# MOTOR_DRIVERS.net
KiCad netlist of a schematic drawn in Altium Designer
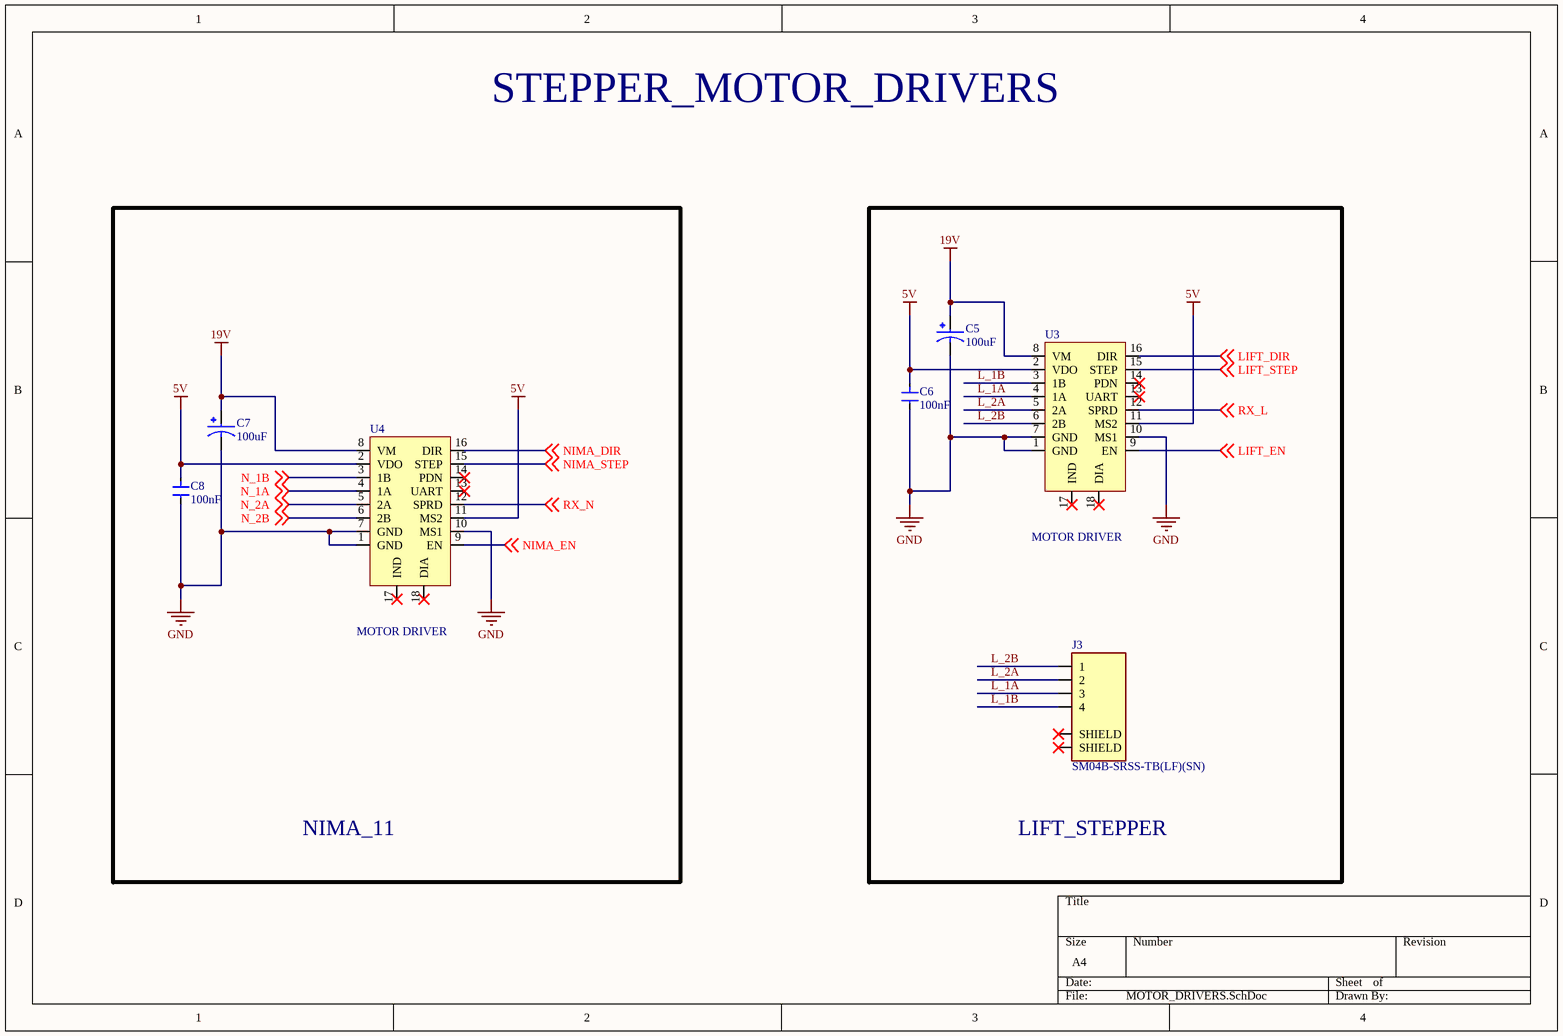
[diagram p0: MOTOR_DRIVERS.SchDoc]

(export (version "E")
  (design (tool "Eeschema 10.0.6"))
  (components
    (comp (ref "C5")
      (value "100uF")
      (footprint "CAP_EEEFTH101XAP")
      (description "100ÂµF 50V Aluminum Electrolytic Capacitors Radial, Can - SMD 340mOhm @ 100kHz 2000 Hrs @ 105Â°C")
      (fields (field (name "PART NUMBER") "EEEFTH101XAP"))
      (libsource (lib "Schlib2") (part "EEEFTH101XAP"))
    )
    (comp (ref "C6")
      (value "100nF")
      (footprint "CAP 0603")
      (fields (field (name "PART NUMBER") "CC0603JRX7R9BB104"))
      (libsource (lib "Schlib2") (part "Capasitor"))
    )
    (comp (ref "C7")
      (value "100uF")
      (footprint "CAP_EEEFTH101XAP")
      (description "100ÂµF 50V Aluminum Electrolytic Capacitors Radial, Can - SMD 340mOhm @ 100kHz 2000 Hrs @ 105Â°C")
      (fields (field (name "PART NUMBER") "EEEFTH101XAP"))
      (libsource (lib "Schlib2") (part "EEEFTH101XAP"))
    )
    (comp (ref "C8")
      (value "100nF")
      (footprint "CAP 0603")
      (fields (field (name "PART NUMBER") "CC0603JRX7R9BB104"))
      (libsource (lib "Schlib2") (part "Capasitor"))
    )
    (comp (ref "J3")
      (value "SM04B-SRSS-TB(LF)(SN)")
      (footprint "CONN-TH_B4B-PH-K-S")
      (description "Connector Header Surface Mount, Right Angle 4 position 0.039 (1.00mm)")
      (fields (field (name "PART NUMBER") "B4B-PH-K-S(LF)(SN)"))
      (libsource (lib "Schlib2") (part "SM04B-SRSS-TB(LF)(SN)"))
    )
    (comp (ref "U3")
      (value "MOTOR DRIVER")
      (footprint "MOTOR DRIVER")
      (libsource (lib "Schlib2") (part "MOTOR DRIVER"))
    )
    (comp (ref "U4")
      (value "MOTOR DRIVER")
      (footprint "MOTOR DRIVER")
      (libsource (lib "Schlib2") (part "MOTOR DRIVER"))
    )
  )
  (nets
    (net (code "1") (name "/L_1A") (class "Default")
      (node (ref "J3") (pin "3") (pinfunction "3_3") (pintype "passive"))
      (node (ref "U3") (pin "4") (pinfunction "1A_4") (pintype "passive"))
    )
    (net (code "2") (name "/L_1B") (class "Default")
      (node (ref "J3") (pin "4") (pinfunction "4_4") (pintype "passive"))
      (node (ref "U3") (pin "3") (pinfunction "1B_3") (pintype "passive"))
    )
    (net (code "3") (name "/L_2A") (class "Default")
      (node (ref "J3") (pin "2") (pinfunction "2_2") (pintype "passive"))
      (node (ref "U3") (pin "5") (pinfunction "2A_5") (pintype "passive"))
    )
    (net (code "4") (name "/L_2B") (class "Default")
      (node (ref "J3") (pin "1") (pinfunction "1_1") (pintype "passive"))
      (node (ref "U3") (pin "6") (pinfunction "2B_6") (pintype "passive"))
    )
    (net (code "5") (name "5V") (class "Default")
      (node (ref "C6") (pin "1") (pinfunction "1_1") (pintype "passive"))
      (node (ref "C8") (pin "1") (pinfunction "1_1") (pintype "passive"))
      (node (ref "U3") (pin "11") (pinfunction "MS2_11") (pintype "passive"))
      (node (ref "U3") (pin "2") (pinfunction "VDO_2") (pintype "passive"))
      (node (ref "U4") (pin "11") (pinfunction "MS2_11") (pintype "passive"))
      (node (ref "U4") (pin "2") (pinfunction "VDO_2") (pintype "passive"))
    )
    (net (code "6") (name "19V") (class "Default")
      (node (ref "C5") (pin "1") (pinfunction "1_1") (pintype "passive"))
      (node (ref "C7") (pin "1") (pinfunction "1_1") (pintype "passive"))
      (node (ref "U3") (pin "8") (pinfunction "VM_8") (pintype "passive"))
      (node (ref "U4") (pin "8") (pinfunction "VM_8") (pintype "passive"))
    )
    (net (code "7") (name "GND") (class "Default")
      (node (ref "C5") (pin "2") (pinfunction "2_2") (pintype "passive"))
      (node (ref "C6") (pin "2") (pinfunction "2_2") (pintype "passive"))
      (node (ref "C7") (pin "2") (pinfunction "2_2") (pintype "passive"))
      (node (ref "C8") (pin "2") (pinfunction "2_2") (pintype "passive"))
      (node (ref "U3") (pin "1") (pinfunction "GND_1") (pintype "passive"))
      (node (ref "U3") (pin "10") (pinfunction "MS1_10") (pintype "passive"))
      (node (ref "U3") (pin "7") (pinfunction "GND_7") (pintype "passive"))
      (node (ref "U4") (pin "1") (pinfunction "GND_1") (pintype "passive"))
      (node (ref "U4") (pin "10") (pinfunction "MS1_10") (pintype "passive"))
      (node (ref "U4") (pin "7") (pinfunction "GND_7") (pintype "passive"))
    )
    (net (code "8") (name "LIFT_DIR") (class "Default")
      (node (ref "U3") (pin "16") (pinfunction "DIR_16") (pintype "passive"))
    )
    (net (code "9") (name "LIFT_EN") (class "Default")
      (node (ref "U3") (pin "9") (pinfunction "EN_9") (pintype "passive"))
    )
    (net (code "10") (name "LIFT_STEP") (class "Default")
      (node (ref "U3") (pin "15") (pinfunction "STEP_15") (pintype "passive"))
    )
    (net (code "11") (name "NIMA_DIR") (class "Default")
      (node (ref "U4") (pin "16") (pinfunction "DIR_16") (pintype "passive"))
    )
    (net (code "12") (name "NIMA_EN") (class "Default")
      (node (ref "U4") (pin "9") (pinfunction "EN_9") (pintype "passive"))
    )
    (net (code "13") (name "NIMA_STEP") (class "Default")
      (node (ref "U4") (pin "15") (pinfunction "STEP_15") (pintype "passive"))
    )
    (net (code "14") (name "N_1A") (class "Default")
      (node (ref "U4") (pin "4") (pinfunction "1A_4") (pintype "passive"))
    )
    (net (code "15") (name "N_1B") (class "Default")
      (node (ref "U4") (pin "3") (pinfunction "1B_3") (pintype "passive"))
    )
    (net (code "16") (name "N_2A") (class "Default")
      (node (ref "U4") (pin "5") (pinfunction "2A_5") (pintype "passive"))
    )
    (net (code "17") (name "N_2B") (class "Default")
      (node (ref "U4") (pin "6") (pinfunction "2B_6") (pintype "passive"))
    )
    (net (code "18") (name "RX_L") (class "Default")
      (node (ref "U3") (pin "12") (pinfunction "SPRD_12") (pintype "passive"))
    )
    (net (code "19") (name "RX_N") (class "Default")
      (node (ref "U4") (pin "12") (pinfunction "SPRD_12") (pintype "passive"))
    )
    (net (code "20") (name "unconnected-(J3-SHIELD-PadS1)") (class "Default")
      (node (ref "J3") (pin "S1") (pinfunction "SHIELD_S1") (pintype "passive+no_connect"))
    )
    (net (code "21") (name "unconnected-(J3-SHIELD-PadS2)") (class "Default")
      (node (ref "J3") (pin "S2") (pinfunction "SHIELD_S2") (pintype "passive+no_connect"))
    )
    (net (code "22") (name "unconnected-(U3-DIA-Pad18)") (class "Default")
      (node (ref "U3") (pin "18") (pinfunction "DIA_18") (pintype "passive+no_connect"))
    )
    (net (code "23") (name "unconnected-(U3-IND-Pad17)") (class "Default")
      (node (ref "U3") (pin "17") (pinfunction "IND_17") (pintype "passive+no_connect"))
    )
    (net (code "24") (name "unconnected-(U3-PDN-Pad14)") (class "Default")
      (node (ref "U3") (pin "14") (pinfunction "PDN_14") (pintype "passive+no_connect"))
    )
    (net (code "25") (name "unconnected-(U3-UART-Pad13)") (class "Default")
      (node (ref "U3") (pin "13") (pinfunction "UART_13") (pintype "passive+no_connect"))
    )
    (net (code "26") (name "unconnected-(U4-DIA-Pad18)") (class "Default")
      (node (ref "U4") (pin "18") (pinfunction "DIA_18") (pintype "passive+no_connect"))
    )
    (net (code "27") (name "unconnected-(U4-IND-Pad17)") (class "Default")
      (node (ref "U4") (pin "17") (pinfunction "IND_17") (pintype "passive+no_connect"))
    )
    (net (code "28") (name "unconnected-(U4-PDN-Pad14)") (class "Default")
      (node (ref "U4") (pin "14") (pinfunction "PDN_14") (pintype "passive+no_connect"))
    )
    (net (code "29") (name "unconnected-(U4-UART-Pad13)") (class "Default")
      (node (ref "U4") (pin "13") (pinfunction "UART_13") (pintype "passive+no_connect"))
    )
  )
)
